# transmissor_v2.net
KiCad netlist of a schematic drawn in EAGLE
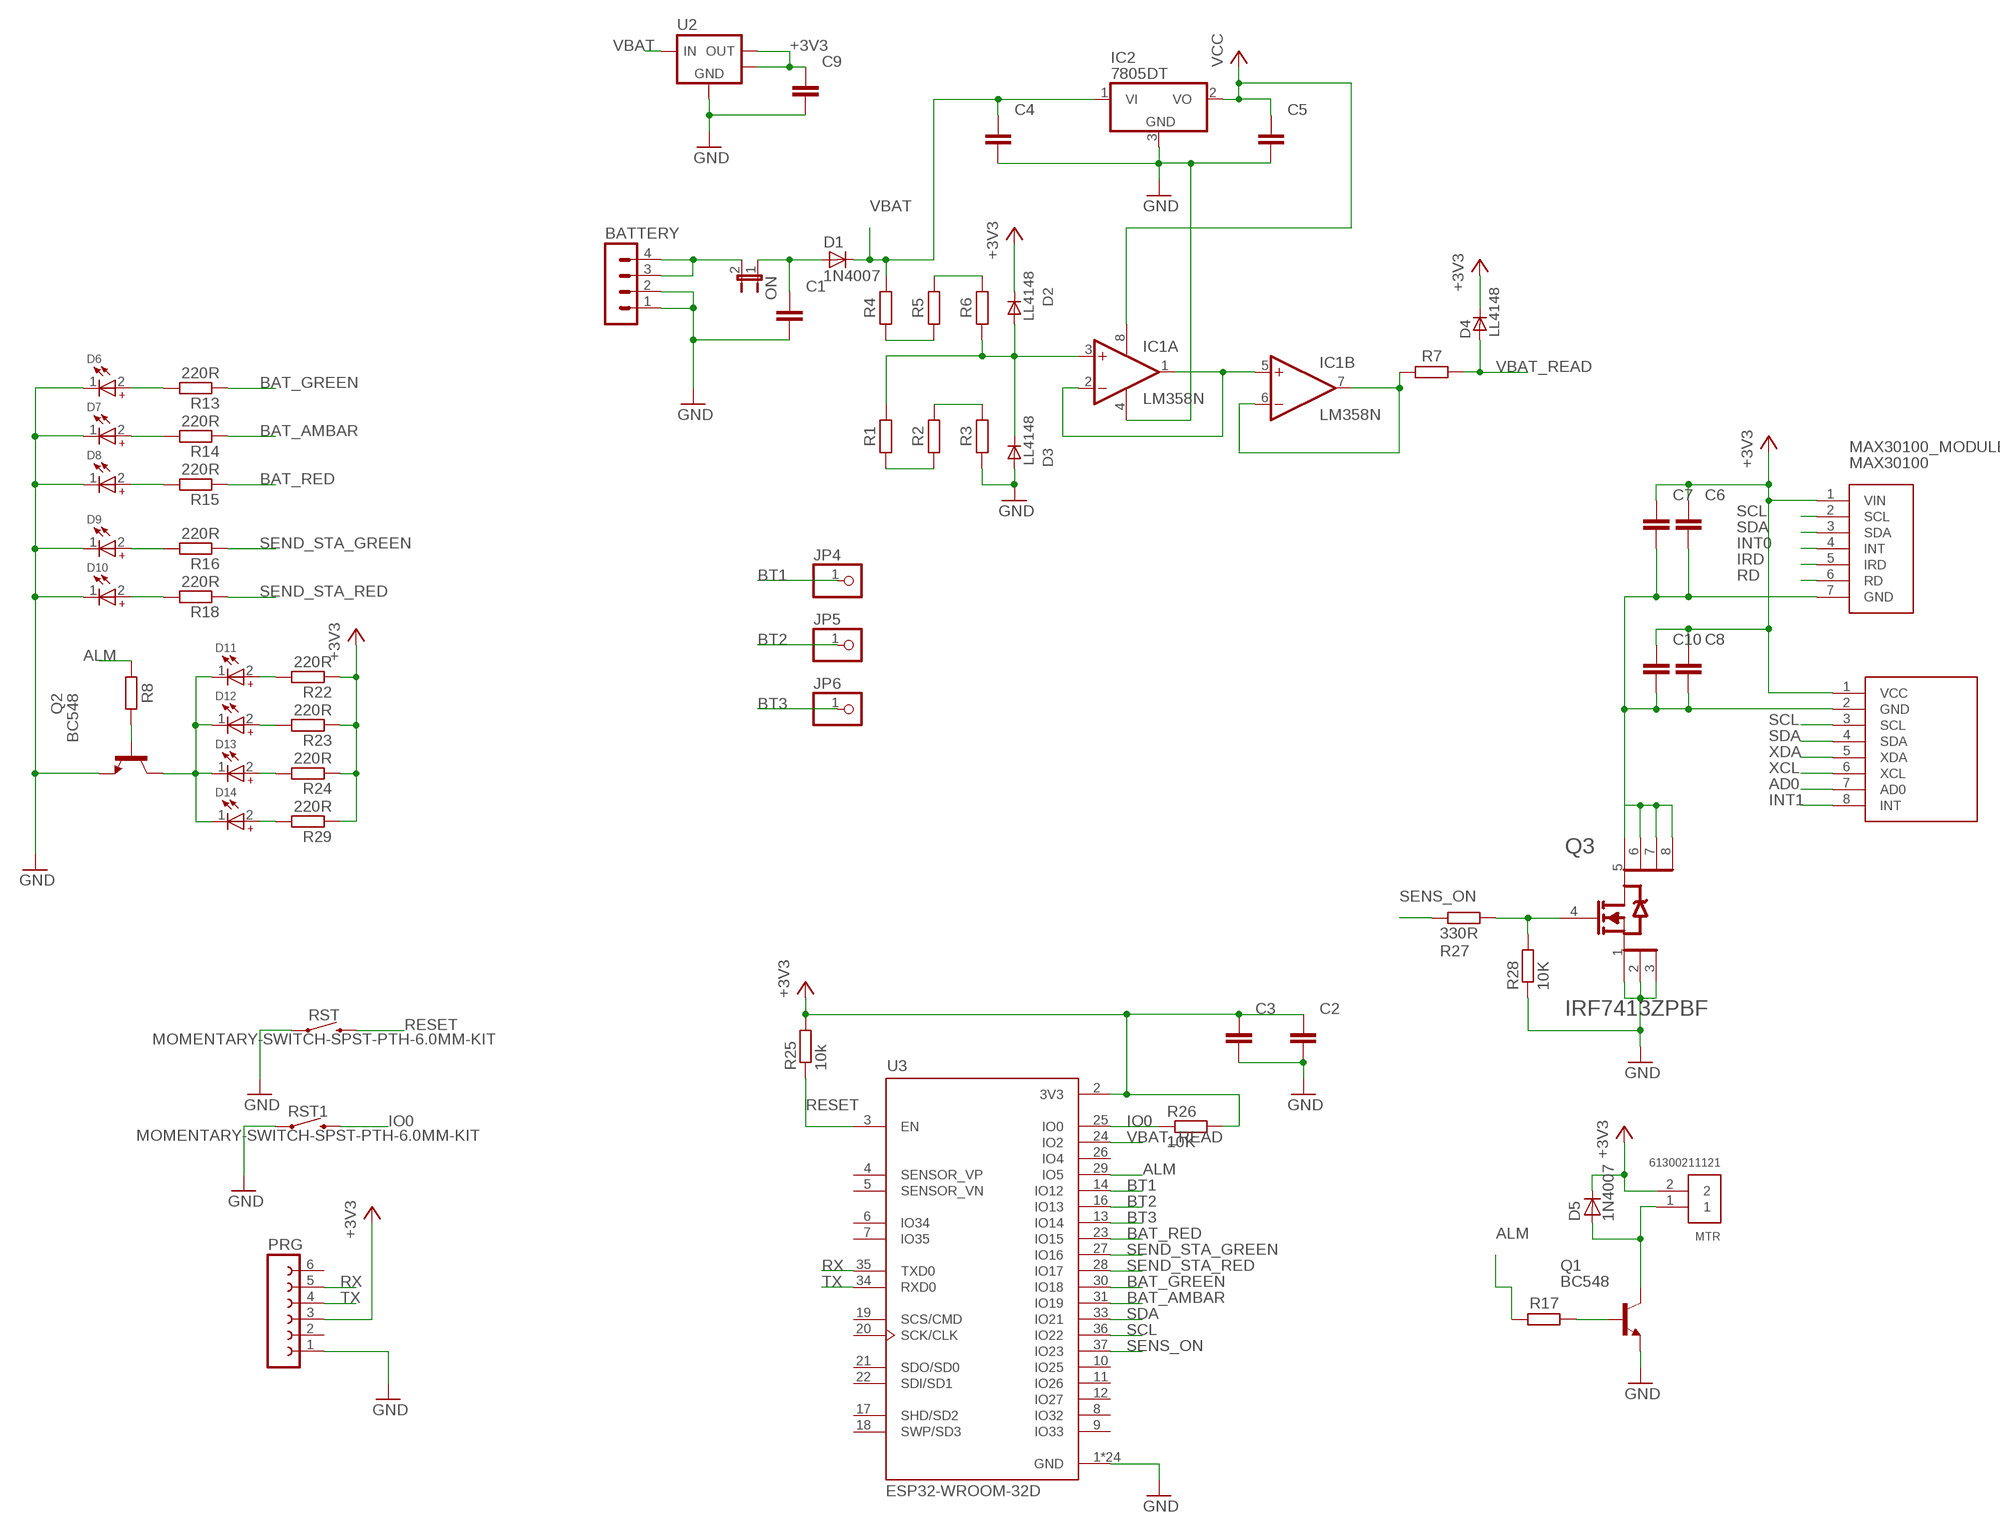
[diagram p0: schematic, sheet 1]

(export (version "E")
  (design (tool "Eeschema 10.0.6"))
  (components
    (comp (ref "BATTERY")
      (value "MA04-1")
      (footprint "eagle-import:MA04-1")
      (libsource (lib "eagle-import") (part "MA04-1"))
    )
    (comp (ref "C1")
      (value "100nF")
      (footprint "eagle-import:CAPC2012X110")
      (libsource (lib "eagle-import") (part "CCHIP-0805(2012-METRIC)_"))
    )
    (comp (ref "C2")
      (value "100nF")
      (footprint "eagle-import:CAPC2012X110")
      (libsource (lib "eagle-import") (part "CCHIP-0805(2012-METRIC)_"))
    )
    (comp (ref "C3")
      (value "100nF")
      (footprint "eagle-import:CAPC2012X110")
      (libsource (lib "eagle-import") (part "CCHIP-0805(2012-METRIC)_"))
    )
    (comp (ref "C4")
      (value "100nF")
      (footprint "eagle-import:CAPC2012X110")
      (libsource (lib "eagle-import") (part "CCHIP-0805(2012-METRIC)_"))
    )
    (comp (ref "C5")
      (value "100nF")
      (footprint "eagle-import:CAPC2012X110")
      (libsource (lib "eagle-import") (part "CCHIP-0805(2012-METRIC)_"))
    )
    (comp (ref "C6")
      (value "100nF")
      (footprint "eagle-import:CAPC2012X110")
      (libsource (lib "eagle-import") (part "CCHIP-0805(2012-METRIC)_"))
    )
    (comp (ref "C7")
      (value "100nF")
      (footprint "eagle-import:CAPC2012X110")
      (libsource (lib "eagle-import") (part "CCHIP-0805(2012-METRIC)_"))
    )
    (comp (ref "C8")
      (value "100nF")
      (footprint "eagle-import:CAPC2012X110")
      (libsource (lib "eagle-import") (part "CCHIP-0805(2012-METRIC)_"))
    )
    (comp (ref "C9")
      (value "100nF")
      (footprint "eagle-import:CAPC2012X110")
      (libsource (lib "eagle-import") (part "CCHIP-0805(2012-METRIC)_"))
    )
    (comp (ref "C10")
      (value "100nF")
      (footprint "eagle-import:CAPC2012X110")
      (libsource (lib "eagle-import") (part "CCHIP-0805(2012-METRIC)_"))
    )
    (comp (ref "D1")
      (value "1N4007")
      (footprint "eagle-import:SMA")
      (libsource (lib "eagle-import") (part "1N4007"))
    )
    (comp (ref "D2")
      (value "LL4148")
      (footprint "eagle-import:SOD80_DO213AA_MINIMELF")
      (libsource (lib "eagle-import") (part "LL4148"))
    )
    (comp (ref "D3")
      (value "LL4148")
      (footprint "eagle-import:SOD80_DO213AA_MINIMELF")
      (libsource (lib "eagle-import") (part "LL4148"))
    )
    (comp (ref "D4")
      (value "LL4148")
      (footprint "eagle-import:SOD80_DO213AA_MINIMELF")
      (libsource (lib "eagle-import") (part "LL4148"))
    )
    (comp (ref "D5")
      (value "1N4007")
      (footprint "eagle-import:SMA")
      (libsource (lib "eagle-import") (part "1N4007"))
    )
    (comp (ref "D6")
      (value "WL-SMCW_0805_150080GS75000")
      (footprint "eagle-import:WL-SMCW_0805")
      (libsource (lib "eagle-import") (part "WL-SMCW_0805_150080GS75000"))
    )
    (comp (ref "D7")
      (value "WL-SMCW_0805_150080AS75000")
      (footprint "eagle-import:WL-SMCW_0805")
      (libsource (lib "eagle-import") (part "WL-SMCW_0805_150080AS75000"))
    )
    (comp (ref "D8")
      (value "WL-SMCW_0805_150080RS75000")
      (footprint "eagle-import:WL-SMCW_0805")
      (libsource (lib "eagle-import") (part "WL-SMCW_0805_150080RS75000"))
    )
    (comp (ref "D9")
      (value "WL-SMCW_0805_150080GS75000")
      (footprint "eagle-import:WL-SMCW_0805")
      (libsource (lib "eagle-import") (part "WL-SMCW_0805_150080GS75000"))
    )
    (comp (ref "D10")
      (value "WL-SMCW_0805_150080RS75000")
      (footprint "eagle-import:WL-SMCW_0805")
      (libsource (lib "eagle-import") (part "WL-SMCW_0805_150080RS75000"))
    )
    (comp (ref "D11")
      (value "WL-SMCW_0805_150080RS75000")
      (footprint "eagle-import:WL-SMCW_0805")
      (libsource (lib "eagle-import") (part "WL-SMCW_0805_150080RS75000"))
    )
    (comp (ref "D12")
      (value "WL-SMCW_0805_150080RS75000")
      (footprint "eagle-import:WL-SMCW_0805")
      (libsource (lib "eagle-import") (part "WL-SMCW_0805_150080RS75000"))
    )
    (comp (ref "D13")
      (value "WL-SMCW_0805_150080RS75000")
      (footprint "eagle-import:WL-SMCW_0805")
      (libsource (lib "eagle-import") (part "WL-SMCW_0805_150080RS75000"))
    )
    (comp (ref "D14")
      (value "WL-SMCW_0805_150080RS75000")
      (footprint "eagle-import:WL-SMCW_0805")
      (libsource (lib "eagle-import") (part "WL-SMCW_0805_150080RS75000"))
    )
    (comp (ref "IC1")
      (value "LM358N")
      (footprint "eagle-import:DIL08")
      (libsource (lib "eagle-import") (part "LM358N"))
    )
    (comp (ref "IC2")
      (value "7805DT")
      (footprint "eagle-import:TO252")
      (libsource (lib "eagle-import") (part "78DT05"))
    )
    (comp (ref "JP4")
      (value "PINHD-1X1")
      (footprint "eagle-import:1X01")
      (libsource (lib "eagle-import") (part "PINHD-1X1"))
    )
    (comp (ref "JP5")
      (value "PINHD-1X1")
      (footprint "eagle-import:1X01")
      (libsource (lib "eagle-import") (part "PINHD-1X1"))
    )
    (comp (ref "JP6")
      (value "PINHD-1X1")
      (footprint "eagle-import:1X01")
      (libsource (lib "eagle-import") (part "PINHD-1X1"))
    )
    (comp (ref "MAX30100")
      (value "MAX30100_MODULE")
      (footprint "eagle-import:MODULE1")
      (libsource (lib "eagle-import") (part "MAX30100_MODULE"))
    )
    (comp (ref "MPU6050")
      (value "MPU6050MODULE")
      (footprint "eagle-import:MODULE2")
      (libsource (lib "eagle-import") (part "MPU6050MODULE"))
    )
    (comp (ref "MTR")
      (value "61300211121")
      (footprint "eagle-import:61300211121")
      (fields
        (field (name "DIGI_KEY_PART_NUMBER") "732-5315-ND")
        (field (name "MANUFACTURER") "Wurth Electronics Inc.")
        (field (name "CREATED_BY") "PCBLayout.com")
      )
      (libsource (lib "eagle-import") (part "61300211121"))
    )
    (comp (ref "ON")
      (value "JP1E")
      (footprint "eagle-import:JP1")
      (libsource (lib "eagle-import") (part "JP1E"))
    )
    (comp (ref "PRG")
      (value "FE06-1")
      (footprint "eagle-import:FE06")
      (libsource (lib "eagle-import") (part "FE06-1"))
    )
    (comp (ref "Q1")
      (value "BC548")
      (footprint "eagle-import:TO92-EBC")
      (libsource (lib "eagle-import") (part "BC548"))
    )
    (comp (ref "Q2")
      (value "BC548")
      (footprint "eagle-import:TO92-EBC")
      (libsource (lib "eagle-import") (part "BC548"))
    )
    (comp (ref "Q3")
      (value "INFINEON_IRF7413ZPBFINFINEON_IRF7413ZPBF_0_0")
      (footprint "eagle-import:INFINEON_IRF7413ZPBF_0")
      (fields
        (field (name "DIGIKEY_PART_NUMBER") "IRF7413ZPBF-ND")
        (field (name "MF") "Infineon")
        (field (name "MOUSER_PART_NUMBER") "942-IRF7413ZPBF")
      )
      (libsource (lib "eagle-import") (part "INFINEON_IRF7413ZPBFINFINEON_IRF7413ZPBF_0_0"))
    )
    (comp (ref "R1")
      (value "2K")
      (footprint "eagle-import:RESC2012X65")
      (libsource (lib "eagle-import") (part "RCHIP-0805(2012-METRIC)_"))
    )
    (comp (ref "R2")
      (value "2K")
      (footprint "eagle-import:RESC2012X65")
      (libsource (lib "eagle-import") (part "RCHIP-0805(2012-METRIC)_"))
    )
    (comp (ref "R3")
      (value "100R")
      (footprint "eagle-import:RESC2012X65")
      (libsource (lib "eagle-import") (part "RCHIP-0805(2012-METRIC)_"))
    )
    (comp (ref "R4")
      (value "3.3K")
      (footprint "eagle-import:RESC2012X65")
      (libsource (lib "eagle-import") (part "RCHIP-0805(2012-METRIC)_"))
    )
    (comp (ref "R5")
      (value "3.3K")
      (footprint "eagle-import:RESC2012X65")
      (libsource (lib "eagle-import") (part "RCHIP-0805(2012-METRIC)_"))
    )
    (comp (ref "R6")
      (value "470R")
      (footprint "eagle-import:RESC2012X65")
      (libsource (lib "eagle-import") (part "RCHIP-0805(2012-METRIC)_"))
    )
    (comp (ref "R7")
      (value "100R")
      (footprint "eagle-import:RESC2012X65")
      (libsource (lib "eagle-import") (part "RCHIP-0805(2012-METRIC)_"))
    )
    (comp (ref "R8")
      (value "330R")
      (footprint "eagle-import:RESC2012X65")
      (libsource (lib "eagle-import") (part "RCHIP-0805(2012-METRIC)_"))
    )
    (comp (ref "R13")
      (value "220R")
      (footprint "eagle-import:R0805")
      (libsource (lib "eagle-import") (part "R-EU_R0805"))
    )
    (comp (ref "R14")
      (value "220R")
      (footprint "eagle-import:R0805")
      (libsource (lib "eagle-import") (part "R-EU_R0805"))
    )
    (comp (ref "R15")
      (value "220R")
      (footprint "eagle-import:R0805")
      (libsource (lib "eagle-import") (part "R-EU_R0805"))
    )
    (comp (ref "R16")
      (value "220R")
      (footprint "eagle-import:R0805")
      (libsource (lib "eagle-import") (part "R-EU_R0805"))
    )
    (comp (ref "R17")
      (value "330R")
      (footprint "eagle-import:RESC2012X65")
      (libsource (lib "eagle-import") (part "RCHIP-0805(2012-METRIC)_"))
    )
    (comp (ref "R18")
      (value "220R")
      (footprint "eagle-import:R0805")
      (libsource (lib "eagle-import") (part "R-EU_R0805"))
    )
    (comp (ref "R22")
      (value "220R")
      (footprint "eagle-import:R0805")
      (libsource (lib "eagle-import") (part "R-EU_R0805"))
    )
    (comp (ref "R23")
      (value "220R")
      (footprint "eagle-import:R0805")
      (libsource (lib "eagle-import") (part "R-EU_R0805"))
    )
    (comp (ref "R24")
      (value "220R")
      (footprint "eagle-import:R0805")
      (libsource (lib "eagle-import") (part "R-EU_R0805"))
    )
    (comp (ref "R25")
      (value "10k")
      (footprint "eagle-import:R0805")
      (libsource (lib "eagle-import") (part "R-EU_R0805"))
    )
    (comp (ref "R26")
      (value "10K")
      (footprint "eagle-import:R0805")
      (libsource (lib "eagle-import") (part "R-EU_R0805"))
    )
    (comp (ref "R27")
      (value "330R")
      (footprint "eagle-import:R0805")
      (libsource (lib "eagle-import") (part "R-EU_R0805"))
    )
    (comp (ref "R28")
      (value "10K")
      (footprint "eagle-import:R0805")
      (libsource (lib "eagle-import") (part "R-EU_R0805"))
    )
    (comp (ref "R29")
      (value "220R")
      (footprint "eagle-import:R0805")
      (libsource (lib "eagle-import") (part "R-EU_R0805"))
    )
    (comp (ref "RST")
      (value "MOMENTARY-SWITCH-SPST-PTH-6.0MM-KIT")
      (footprint "eagle-import:TACTILE_SWITCH_PTH_6.0MM_KIT")
      (libsource (lib "eagle-import") (part "MOMENTARY-SWITCH-SPST-PTH-6.0MM-KIT"))
    )
    (comp (ref "RST1")
      (value "MOMENTARY-SWITCH-SPST-PTH-6.0MM-KIT")
      (footprint "eagle-import:TACTILE_SWITCH_PTH_6.0MM_KIT")
      (libsource (lib "eagle-import") (part "MOMENTARY-SWITCH-SPST-PTH-6.0MM-KIT"))
    )
    (comp (ref "U2")
      (value "LM1117-SOT223")
      (footprint "eagle-import:SOT-223-3")
      (libsource (lib "eagle-import") (part "LM1117-SOT223"))
    )
    (comp (ref "U3")
      (value "ESP32-WROOM-32D")
      (footprint "eagle-import:MODULE_ESP32-WROOM-32D")
      (fields (field (name "MF") "Espressif Systems"))
      (libsource (lib "eagle-import") (part "ESP32-WROOM-32D"))
    )
  )
  (nets
    (net (code "1") (name "+3V3") (class "Default")
      (node (ref "C10") (pin "1") (pinfunction "1_1") (pintype "passive"))
      (node (ref "C2") (pin "1") (pinfunction "1_1") (pintype "passive"))
      (node (ref "C3") (pin "1") (pinfunction "1_1") (pintype "passive"))
      (node (ref "C6") (pin "1") (pinfunction "1_1") (pintype "passive"))
      (node (ref "C7") (pin "1") (pinfunction "1_1") (pintype "passive"))
      (node (ref "C8") (pin "1") (pinfunction "1_1") (pintype "passive"))
      (node (ref "C9") (pin "1") (pinfunction "1_1") (pintype "passive"))
      (node (ref "D2") (pin "C") (pinfunction "C_C") (pintype "passive"))
      (node (ref "D4") (pin "C") (pinfunction "C_C") (pintype "passive"))
      (node (ref "D5") (pin "K") (pinfunction "C_K") (pintype "passive"))
      (node (ref "MAX30100") (pin "1") (pinfunction "VIN_1") (pintype "bidirectional"))
      (node (ref "MPU6050") (pin "1") (pinfunction "VCC_1") (pintype "bidirectional"))
      (node (ref "MTR") (pin "2") (pinfunction "2_2") (pintype "passive"))
      (node (ref "PRG") (pin "3") (pinfunction "3_3") (pintype "passive"))
      (node (ref "R22") (pin "1") (pinfunction "1_1") (pintype "passive"))
      (node (ref "R23") (pin "1") (pinfunction "1_1") (pintype "passive"))
      (node (ref "R24") (pin "1") (pinfunction "1_1") (pintype "passive"))
      (node (ref "R25") (pin "2") (pinfunction "2_2") (pintype "passive"))
      (node (ref "R26") (pin "2") (pinfunction "2_2") (pintype "passive"))
      (node (ref "R29") (pin "1") (pinfunction "1_1") (pintype "passive"))
      (node (ref "U2") (pin "2") (pinfunction "VOUT_2") (pintype "power_in"))
      (node (ref "U2") (pin "4") (pinfunction "HEATSINK_4") (pintype "power_in"))
      (node (ref "U3") (pin "2") (pinfunction "3V3_2") (pintype "power_in"))
    )
    (net (code "2") (name "/AD0") (class "Default")
      (node (ref "MPU6050") (pin "7") (pinfunction "AD0_7") (pintype "bidirectional"))
    )
    (net (code "3") (name "/ALM") (class "Default")
      (node (ref "R17") (pin "1") (pinfunction "1_1") (pintype "passive"))
      (node (ref "R8") (pin "1") (pinfunction "1_1") (pintype "passive"))
      (node (ref "U3") (pin "29") (pinfunction "IO5_29") (pintype "bidirectional"))
    )
    (net (code "4") (name "/BAT_AMBAR") (class "Default")
      (node (ref "R14") (pin "1") (pinfunction "1_1") (pintype "passive"))
      (node (ref "U3") (pin "31") (pinfunction "IO19_31") (pintype "bidirectional"))
    )
    (net (code "5") (name "/BAT_GREEN") (class "Default")
      (node (ref "R13") (pin "1") (pinfunction "1_1") (pintype "passive"))
      (node (ref "U3") (pin "30") (pinfunction "IO18_30") (pintype "bidirectional"))
    )
    (net (code "6") (name "/BAT_RED") (class "Default")
      (node (ref "R15") (pin "1") (pinfunction "1_1") (pintype "passive"))
      (node (ref "U3") (pin "23") (pinfunction "IO15_23") (pintype "bidirectional"))
    )
    (net (code "7") (name "/BT1") (class "Default")
      (node (ref "JP4") (pin "1") (pinfunction "1_1") (pintype "passive"))
      (node (ref "U3") (pin "14") (pinfunction "IO12_14") (pintype "bidirectional"))
    )
    (net (code "8") (name "/BT2") (class "Default")
      (node (ref "JP5") (pin "1") (pinfunction "1_1") (pintype "passive"))
      (node (ref "U3") (pin "16") (pinfunction "IO13_16") (pintype "bidirectional"))
    )
    (net (code "9") (name "/BT3") (class "Default")
      (node (ref "JP6") (pin "1") (pinfunction "1_1") (pintype "passive"))
      (node (ref "U3") (pin "13") (pinfunction "IO14_13") (pintype "bidirectional"))
    )
    (net (code "10") (name "/INT0") (class "Default")
      (node (ref "MAX30100") (pin "4") (pinfunction "INT_4") (pintype "bidirectional"))
    )
    (net (code "11") (name "/INT1") (class "Default")
      (node (ref "MPU6050") (pin "8") (pinfunction "INT_8") (pintype "bidirectional"))
    )
    (net (code "12") (name "/IO0") (class "Default")
      (node (ref "R26") (pin "1") (pinfunction "1_1") (pintype "passive"))
      (node (ref "RST1") (pin "3") (pinfunction "2_3") (pintype "passive"))
      (node (ref "U3") (pin "25") (pinfunction "IO0_25") (pintype "bidirectional"))
    )
    (net (code "13") (name "/IRD") (class "Default")
      (node (ref "MAX30100") (pin "5") (pinfunction "IRD_5") (pintype "bidirectional"))
    )
    (net (code "14") (name "/RD") (class "Default")
      (node (ref "MAX30100") (pin "6") (pinfunction "RD_6") (pintype "bidirectional"))
    )
    (net (code "15") (name "/RESET") (class "Default")
      (node (ref "R25") (pin "1") (pinfunction "1_1") (pintype "passive"))
      (node (ref "RST") (pin "3") (pinfunction "2_3") (pintype "passive"))
      (node (ref "U3") (pin "3") (pinfunction "EN_3") (pintype "input"))
    )
    (net (code "16") (name "/RX") (class "Default")
      (node (ref "PRG") (pin "5") (pinfunction "5_5") (pintype "passive"))
      (node (ref "U3") (pin "35") (pinfunction "TXD0_35") (pintype "bidirectional"))
    )
    (net (code "17") (name "/SCL") (class "Default")
      (node (ref "MAX30100") (pin "2") (pinfunction "SCL_2") (pintype "bidirectional"))
      (node (ref "MPU6050") (pin "3") (pinfunction "SCL_3") (pintype "bidirectional"))
      (node (ref "U3") (pin "36") (pinfunction "IO22_36") (pintype "bidirectional"))
    )
    (net (code "18") (name "/SDA") (class "Default")
      (node (ref "MAX30100") (pin "3") (pinfunction "SDA_3") (pintype "bidirectional"))
      (node (ref "MPU6050") (pin "4") (pinfunction "SDA_4") (pintype "bidirectional"))
      (node (ref "U3") (pin "33") (pinfunction "IO21_33") (pintype "bidirectional"))
    )
    (net (code "19") (name "/SEND_STA_GREEN") (class "Default")
      (node (ref "R16") (pin "1") (pinfunction "1_1") (pintype "passive"))
      (node (ref "U3") (pin "27") (pinfunction "IO16_27") (pintype "bidirectional"))
    )
    (net (code "20") (name "/SEND_STA_RED") (class "Default")
      (node (ref "R18") (pin "1") (pinfunction "1_1") (pintype "passive"))
      (node (ref "U3") (pin "28") (pinfunction "IO17_28") (pintype "bidirectional"))
    )
    (net (code "21") (name "/SENS_ON") (class "Default")
      (node (ref "R27") (pin "1") (pinfunction "1_1") (pintype "passive"))
      (node (ref "U3") (pin "37") (pinfunction "IO23_37") (pintype "bidirectional"))
    )
    (net (code "22") (name "/TX") (class "Default")
      (node (ref "PRG") (pin "4") (pinfunction "4_4") (pintype "passive"))
      (node (ref "U3") (pin "34") (pinfunction "RXD0_34") (pintype "bidirectional"))
    )
    (net (code "23") (name "/VBAT") (class "Default")
      (node (ref "C4") (pin "1") (pinfunction "1_1") (pintype "passive"))
      (node (ref "D1") (pin "K") (pinfunction "C_K") (pintype "passive"))
      (node (ref "IC2") (pin "1") (pinfunction "VI_1") (pintype "input"))
      (node (ref "R4") (pin "2") (pinfunction "2_2") (pintype "passive"))
      (node (ref "U2") (pin "3") (pinfunction "VIN_3") (pintype "power_in"))
    )
    (net (code "24") (name "/VBAT_READ") (class "Default")
      (node (ref "D4") (pin "A") (pinfunction "A_A") (pintype "passive"))
      (node (ref "R7") (pin "2") (pinfunction "2_2") (pintype "passive"))
      (node (ref "U3") (pin "24") (pinfunction "IO2_24") (pintype "bidirectional"))
    )
    (net (code "25") (name "/XCL") (class "Default")
      (node (ref "MPU6050") (pin "6") (pinfunction "XCL_6") (pintype "bidirectional"))
    )
    (net (code "26") (name "/XDA") (class "Default")
      (node (ref "MPU6050") (pin "5") (pinfunction "XDA_5") (pintype "bidirectional"))
    )
    (net (code "27") (name "GND") (class "Default")
      (node (ref "BATTERY") (pin "1") (pinfunction "1_1") (pintype "passive"))
      (node (ref "BATTERY") (pin "2") (pinfunction "2_2") (pintype "passive"))
      (node (ref "C1") (pin "2") (pinfunction "2_2") (pintype "passive"))
      (node (ref "C2") (pin "2") (pinfunction "2_2") (pintype "passive"))
      (node (ref "C3") (pin "2") (pinfunction "2_2") (pintype "passive"))
      (node (ref "C4") (pin "2") (pinfunction "2_2") (pintype "passive"))
      (node (ref "C5") (pin "2") (pinfunction "2_2") (pintype "passive"))
      (node (ref "C9") (pin "2") (pinfunction "2_2") (pintype "passive"))
      (node (ref "D10") (pin "1") (pinfunction "-_1") (pintype "passive"))
      (node (ref "D3") (pin "A") (pinfunction "A_A") (pintype "passive"))
      (node (ref "D6") (pin "1") (pinfunction "-_1") (pintype "passive"))
      (node (ref "D7") (pin "1") (pinfunction "-_1") (pintype "passive"))
      (node (ref "D8") (pin "1") (pinfunction "-_1") (pintype "passive"))
      (node (ref "D9") (pin "1") (pinfunction "-_1") (pintype "passive"))
      (node (ref "IC1") (pin "4") (pinfunction "V-_4") (pintype "power_in"))
      (node (ref "IC2") (pin "3") (pinfunction "GND_3") (pintype "passive"))
      (node (ref "PRG") (pin "1") (pinfunction "1_1") (pintype "passive"))
      (node (ref "Q1") (pin "E") (pinfunction "E_E") (pintype "passive"))
      (node (ref "Q2") (pin "E") (pinfunction "E_E") (pintype "passive"))
      (node (ref "Q3") (pin "1") (pinfunction "1_S_1") (pintype "bidirectional"))
      (node (ref "Q3") (pin "2") (pinfunction "2_S_2") (pintype "bidirectional"))
      (node (ref "Q3") (pin "3") (pinfunction "3_S_3") (pintype "bidirectional"))
      (node (ref "R28") (pin "1") (pinfunction "1_1") (pintype "passive"))
      (node (ref "R3") (pin "1") (pinfunction "1_1") (pintype "passive"))
      (node (ref "RST") (pin "1") (pinfunction "1_1") (pintype "passive"))
      (node (ref "RST1") (pin "1") (pinfunction "1_1") (pintype "passive"))
      (node (ref "U2") (pin "1") (pinfunction "GND_1") (pintype "power_in"))
      (node (ref "U3") (pin "1") (pinfunction "GND_1") (pintype "power_in"))
      (node (ref "U3") (pin "15") (pinfunction "GND_15") (pintype "power_in"))
      (node (ref "U3") (pin "38") (pinfunction "GND_38") (pintype "power_in"))
      (node (ref "U3") (pin "39_1") (pinfunction "GND_39_1") (pintype "power_in"))
      (node (ref "U3") (pin "39_10") (pinfunction "GND_39_10") (pintype "power_in"))
      (node (ref "U3") (pin "39_11") (pinfunction "GND_39_11") (pintype "power_in"))
      (node (ref "U3") (pin "39_12") (pinfunction "GND_39_12") (pintype "power_in"))
      (node (ref "U3") (pin "39_13") (pinfunction "GND_39_13") (pintype "power_in"))
      (node (ref "U3") (pin "39_14") (pinfunction "GND_39_14") (pintype "power_in"))
      (node (ref "U3") (pin "39_15") (pinfunction "GND_39_15") (pintype "power_in"))
      (node (ref "U3") (pin "39_16") (pinfunction "GND_39_16") (pintype "power_in"))
      (node (ref "U3") (pin "39_17") (pinfunction "GND_39_17") (pintype "power_in"))
      (node (ref "U3") (pin "39_18") (pinfunction "GND_39_18") (pintype "power_in"))
      (node (ref "U3") (pin "39_19") (pinfunction "GND_39_19") (pintype "power_in"))
      (node (ref "U3") (pin "39_2") (pinfunction "GND_39_2") (pintype "power_in"))
      (node (ref "U3") (pin "39_20") (pinfunction "GND_39_20") (pintype "power_in"))
      (node (ref "U3") (pin "39_21") (pinfunction "GND_39_21") (pintype "power_in"))
      (node (ref "U3") (pin "39_3") (pinfunction "GND_39_3") (pintype "power_in"))
      (node (ref "U3") (pin "39_4") (pinfunction "GND_39_4") (pintype "power_in"))
      (node (ref "U3") (pin "39_5") (pinfunction "GND_39_5") (pintype "power_in"))
      (node (ref "U3") (pin "39_6") (pinfunction "GND_39_6") (pintype "power_in"))
      (node (ref "U3") (pin "39_7") (pinfunction "GND_39_7") (pintype "power_in"))
      (node (ref "U3") (pin "39_8") (pinfunction "GND_39_8") (pintype "power_in"))
      (node (ref "U3") (pin "39_9") (pinfunction "GND_39_9") (pintype "power_in"))
    )
    (net (code "28") (name "Net-(BATTERY-Pad3)") (class "Default")
      (node (ref "BATTERY") (pin "3") (pinfunction "3_3") (pintype "passive"))
      (node (ref "BATTERY") (pin "4") (pinfunction "4_4") (pintype "passive"))
      (node (ref "ON") (pin "2") (pinfunction "2_2") (pintype "passive"))
    )
    (net (code "29") (name "Net-(C1-Pad1)") (class "Default")
      (node (ref "C1") (pin "1") (pinfunction "1_1") (pintype "passive"))
      (node (ref "D1") (pin "A") (pinfunction "A_A") (pintype "passive"))
      (node (ref "ON") (pin "1") (pinfunction "1_1") (pintype "passive"))
    )
    (net (code "30") (name "Net-(D5-PadA)") (class "Default")
      (node (ref "D5") (pin "A") (pinfunction "A_A") (pintype "passive"))
      (node (ref "MTR") (pin "1") (pinfunction "1_1") (pintype "passive"))
      (node (ref "Q1") (pin "C") (pinfunction "C_C") (pintype "passive"))
    )
    (net (code "31") (name "Net-(D6-+)") (class "Default")
      (node (ref "D6") (pin "2") (pinfunction "+_2") (pintype "passive"))
      (node (ref "R13") (pin "2") (pinfunction "2_2") (pintype "passive"))
    )
    (net (code "32") (name "Net-(D7-+)") (class "Default")
      (node (ref "D7") (pin "2") (pinfunction "+_2") (pintype "passive"))
      (node (ref "R14") (pin "2") (pinfunction "2_2") (pintype "passive"))
    )
    (net (code "33") (name "Net-(D8-+)") (class "Default")
      (node (ref "D8") (pin "2") (pinfunction "+_2") (pintype "passive"))
      (node (ref "R15") (pin "2") (pinfunction "2_2") (pintype "passive"))
    )
    (net (code "34") (name "Net-(D9-+)") (class "Default")
      (node (ref "D9") (pin "2") (pinfunction "+_2") (pintype "passive"))
      (node (ref "R16") (pin "2") (pinfunction "2_2") (pintype "passive"))
    )
    (net (code "35") (name "Net-(D10-+)") (class "Default")
      (node (ref "D10") (pin "2") (pinfunction "+_2") (pintype "passive"))
      (node (ref "R18") (pin "2") (pinfunction "2_2") (pintype "passive"))
    )
    (net (code "36") (name "Net-(D11-+)") (class "Default")
      (node (ref "D11") (pin "2") (pinfunction "+_2") (pintype "passive"))
      (node (ref "R22") (pin "2") (pinfunction "2_2") (pintype "passive"))
    )
    (net (code "37") (name "Net-(D11--)") (class "Default")
      (node (ref "D11") (pin "1") (pinfunction "-_1") (pintype "passive"))
      (node (ref "D12") (pin "1") (pinfunction "-_1") (pintype "passive"))
      (node (ref "D13") (pin "1") (pinfunction "-_1") (pintype "passive"))
      (node (ref "D14") (pin "1") (pinfunction "-_1") (pintype "passive"))
      (node (ref "Q2") (pin "C") (pinfunction "C_C") (pintype "passive"))
    )
    (net (code "38") (name "Net-(D12-+)") (class "Default")
      (node (ref "D12") (pin "2") (pinfunction "+_2") (pintype "passive"))
      (node (ref "R23") (pin "2") (pinfunction "2_2") (pintype "passive"))
    )
    (net (code "39") (name "Net-(D13-+)") (class "Default")
      (node (ref "D13") (pin "2") (pinfunction "+_2") (pintype "passive"))
      (node (ref "R24") (pin "2") (pinfunction "2_2") (pintype "passive"))
    )
    (net (code "40") (name "Net-(D14-+)") (class "Default")
      (node (ref "D14") (pin "2") (pinfunction "+_2") (pintype "passive"))
      (node (ref "R29") (pin "2") (pinfunction "2_2") (pintype "passive"))
    )
    (net (code "41") (name "Net-(IC1A-+IN)") (class "Default")
      (node (ref "D2") (pin "A") (pinfunction "A_A") (pintype "passive"))
      (node (ref "D3") (pin "C") (pinfunction "C_C") (pintype "passive"))
      (node (ref "IC1") (pin "3") (pinfunction "+IN_3") (pintype "input"))
      (node (ref "R1") (pin "2") (pinfunction "2_2") (pintype "passive"))
      (node (ref "R6") (pin "1") (pinfunction "1_1") (pintype "passive"))
    )
    (net (code "42") (name "Net-(IC1A--IN)") (class "Default")
      (node (ref "IC1") (pin "1") (pinfunction "OUT_1") (pintype "output"))
      (node (ref "IC1") (pin "2") (pinfunction "-IN_2") (pintype "input"))
      (node (ref "IC1") (pin "5") (pinfunction "+IN_5") (pintype "input"))
    )
    (net (code "43") (name "Net-(IC1B--IN)") (class "Default")
      (node (ref "IC1") (pin "6") (pinfunction "-IN_6") (pintype "input"))
      (node (ref "IC1") (pin "7") (pinfunction "OUT_7") (pintype "output"))
      (node (ref "R7") (pin "1") (pinfunction "1_1") (pintype "passive"))
    )
    (net (code "44") (name "Net-(MAX30100-GND)") (class "Default")
      (node (ref "C10") (pin "2") (pinfunction "2_2") (pintype "passive"))
      (node (ref "C6") (pin "2") (pinfunction "2_2") (pintype "passive"))
      (node (ref "C7") (pin "2") (pinfunction "2_2") (pintype "passive"))
      (node (ref "C8") (pin "2") (pinfunction "2_2") (pintype "passive"))
      (node (ref "MAX30100") (pin "7") (pinfunction "GND_7") (pintype "bidirectional"))
      (node (ref "MPU6050") (pin "2") (pinfunction "GND_2") (pintype "bidirectional"))
      (node (ref "Q3") (pin "5") (pinfunction "1_D_5") (pintype "bidirectional"))
      (node (ref "Q3") (pin "6") (pinfunction "2_D_6") (pintype "bidirectional"))
      (node (ref "Q3") (pin "7") (pinfunction "3_D_7") (pintype "bidirectional"))
      (node (ref "Q3") (pin "8") (pinfunction "4_D_8") (pintype "bidirectional"))
    )
    (net (code "45") (name "Net-(Q1-PadB)") (class "Default")
      (node (ref "Q1") (pin "B") (pinfunction "B_B") (pintype "passive"))
      (node (ref "R17") (pin "2") (pinfunction "2_2") (pintype "passive"))
    )
    (net (code "46") (name "Net-(Q2-PadB)") (class "Default")
      (node (ref "Q2") (pin "B") (pinfunction "B_B") (pintype "passive"))
      (node (ref "R8") (pin "2") (pinfunction "2_2") (pintype "passive"))
    )
    (net (code "47") (name "Net-(Q3-G)") (class "Default")
      (node (ref "Q3") (pin "4") (pinfunction "G_4") (pintype "bidirectional"))
      (node (ref "R27") (pin "2") (pinfunction "2_2") (pintype "passive"))
      (node (ref "R28") (pin "2") (pinfunction "2_2") (pintype "passive"))
    )
    (net (code "48") (name "Net-(R1-Pad1)") (class "Default")
      (node (ref "R1") (pin "1") (pinfunction "1_1") (pintype "passive"))
      (node (ref "R2") (pin "1") (pinfunction "1_1") (pintype "passive"))
    )
    (net (code "49") (name "Net-(R2-Pad2)") (class "Default")
      (node (ref "R2") (pin "2") (pinfunction "2_2") (pintype "passive"))
      (node (ref "R3") (pin "2") (pinfunction "2_2") (pintype "passive"))
    )
    (net (code "50") (name "Net-(R4-Pad1)") (class "Default")
      (node (ref "R4") (pin "1") (pinfunction "1_1") (pintype "passive"))
      (node (ref "R5") (pin "1") (pinfunction "1_1") (pintype "passive"))
    )
    (net (code "51") (name "Net-(R5-Pad2)") (class "Default")
      (node (ref "R5") (pin "2") (pinfunction "2_2") (pintype "passive"))
      (node (ref "R6") (pin "2") (pinfunction "2_2") (pintype "passive"))
    )
    (net (code "52") (name "VCC") (class "Default")
      (node (ref "C5") (pin "1") (pinfunction "1_1") (pintype "passive"))
      (node (ref "IC1") (pin "8") (pinfunction "V+_8") (pintype "power_in"))
      (node (ref "IC2") (pin "2") (pinfunction "VO_2") (pintype "passive"))
    )
    (net (code "53") (name "unconnected-(PRG-Pad2)") (class "Default")
      (node (ref "PRG") (pin "2") (pinfunction "2_2") (pintype "passive"))
    )
    (net (code "54") (name "unconnected-(PRG-Pad6)") (class "Default")
      (node (ref "PRG") (pin "6") (pinfunction "6_6") (pintype "passive"))
    )
    (net (code "55") (name "unconnected-(U3-IO4-Pad26)") (class "Default")
      (node (ref "U3") (pin "26") (pinfunction "IO4_26") (pintype "bidirectional"))
    )
    (net (code "56") (name "unconnected-(U3-IO25-Pad10)") (class "Default")
      (node (ref "U3") (pin "10") (pinfunction "IO25_10") (pintype "bidirectional"))
    )
    (net (code "57") (name "unconnected-(U3-IO26-Pad11)") (class "Default")
      (node (ref "U3") (pin "11") (pinfunction "IO26_11") (pintype "bidirectional"))
    )
    (net (code "58") (name "unconnected-(U3-IO27-Pad12)") (class "Default")
      (node (ref "U3") (pin "12") (pinfunction "IO27_12") (pintype "bidirectional"))
    )
    (net (code "59") (name "unconnected-(U3-IO32-Pad8)") (class "Default")
      (node (ref "U3") (pin "8") (pinfunction "IO32_8") (pintype "bidirectional"))
    )
    (net (code "60") (name "unconnected-(U3-IO33-Pad9)") (class "Default")
      (node (ref "U3") (pin "9") (pinfunction "IO33_9") (pintype "bidirectional"))
    )
    (net (code "61") (name "unconnected-(U3-IO34-Pad6)") (class "Default")
      (node (ref "U3") (pin "6") (pinfunction "IO34_6") (pintype "input"))
    )
    (net (code "62") (name "unconnected-(U3-IO35-Pad7)") (class "Default")
      (node (ref "U3") (pin "7") (pinfunction "IO35_7") (pintype "input"))
    )
    (net (code "63") (name "unconnected-(U3-SCK{slash}CLK-Pad20)") (class "Default")
      (node (ref "U3") (pin "20") (pinfunction "SCK/CLK_20") (pintype "bidirectional"))
    )
    (net (code "64") (name "unconnected-(U3-SCS{slash}CMD-Pad19)") (class "Default")
      (node (ref "U3") (pin "19") (pinfunction "SCS/CMD_19") (pintype "bidirectional"))
    )
    (net (code "65") (name "unconnected-(U3-SDI{slash}SD1-Pad22)") (class "Default")
      (node (ref "U3") (pin "22") (pinfunction "SDI/SD1_22") (pintype "bidirectional"))
    )
    (net (code "66") (name "unconnected-(U3-SDO{slash}SD0-Pad21)") (class "Default")
      (node (ref "U3") (pin "21") (pinfunction "SDO/SD0_21") (pintype "bidirectional"))
    )
    (net (code "67") (name "unconnected-(U3-SENSOR_VN-Pad5)") (class "Default")
      (node (ref "U3") (pin "5") (pinfunction "SENSOR_VN_5") (pintype "input"))
    )
    (net (code "68") (name "unconnected-(U3-SENSOR_VP-Pad4)") (class "Default")
      (node (ref "U3") (pin "4") (pinfunction "SENSOR_VP_4") (pintype "input"))
    )
    (net (code "69") (name "unconnected-(U3-SHD{slash}SD2-Pad17)") (class "Default")
      (node (ref "U3") (pin "17") (pinfunction "SHD/SD2_17") (pintype "bidirectional"))
    )
    (net (code "70") (name "unconnected-(U3-SWP{slash}SD3-Pad18)") (class "Default")
      (node (ref "U3") (pin "18") (pinfunction "SWP/SD3_18") (pintype "bidirectional"))
    )
  )
)
